# Charger_boost_LDO.net
KiCad netlist of a schematic drawn in Altium Designer
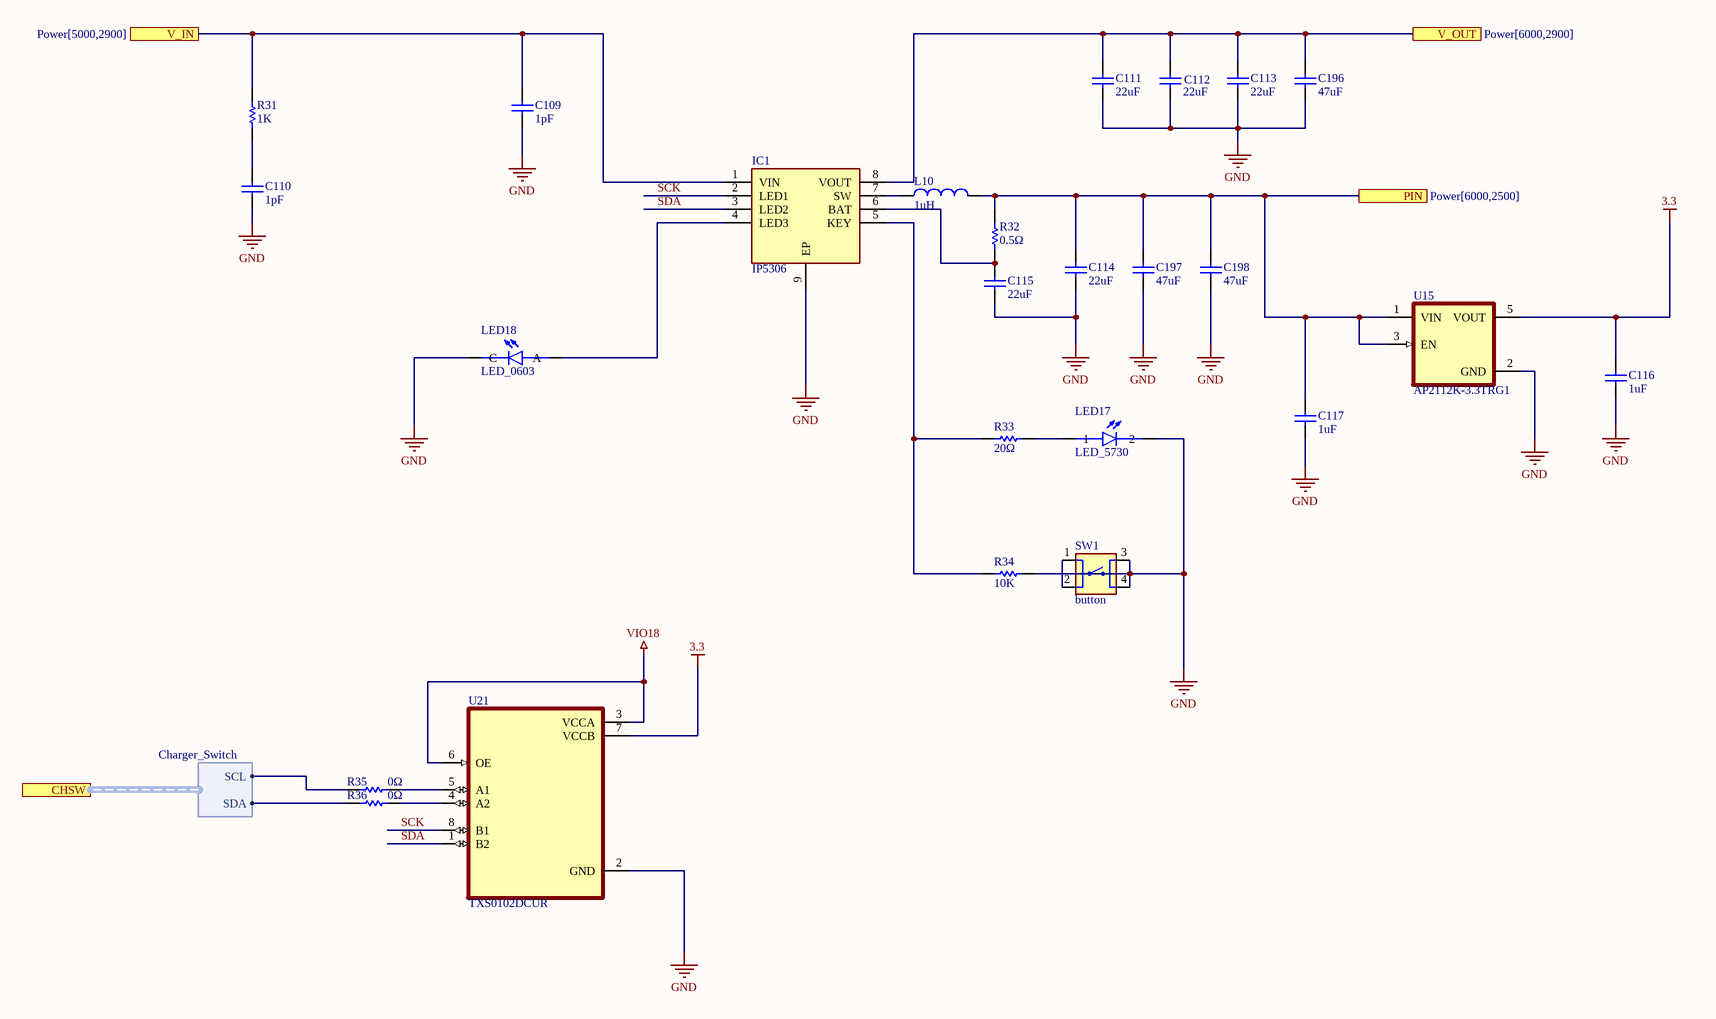
[diagram p0: Charger_boost_LDO.SchDoc]

(export (version "E")
  (design (tool "Eeschema 10.0.6"))
  (components
    (comp (ref "C109")
      (value "1pF")
      (footprint "C0402")
      (fields (field (name "Comment") "C0402"))
      (libsource (lib "kit") (part "C0402"))
    )
    (comp (ref "C110")
      (value "1pF")
      (footprint "C0402")
      (fields (field (name "Comment") "C0402"))
      (libsource (lib "kit") (part "C0402"))
    )
    (comp (ref "C111")
      (value "22uF")
      (footprint "C1210")
      (fields (field (name "Comment") "C1210"))
      (libsource (lib "kit") (part "C1210"))
    )
    (comp (ref "C112")
      (value "22uF")
      (footprint "C1210")
      (fields (field (name "Comment") "C1210"))
      (libsource (lib "kit") (part "C1210"))
    )
    (comp (ref "C113")
      (value "22uF")
      (footprint "C1210")
      (fields (field (name "Comment") "C1210"))
      (libsource (lib "kit") (part "C1210"))
    )
    (comp (ref "C114")
      (value "22uF")
      (footprint "C1210")
      (fields (field (name "Comment") "C1210"))
      (libsource (lib "kit") (part "C1210"))
    )
    (comp (ref "C115")
      (value "22uF")
      (footprint "C1210")
      (fields (field (name "Comment") "C1210"))
      (libsource (lib "kit") (part "C1210"))
    )
    (comp (ref "C116")
      (value "1uF")
      (footprint "C0805")
      (fields (field (name "Comment") "C0805"))
      (libsource (lib "kit") (part "C0805"))
    )
    (comp (ref "C117")
      (value "1uF")
      (footprint "C0805")
      (fields (field (name "Comment") "C0805"))
      (libsource (lib "kit") (part "C0805"))
    )
    (comp (ref "C196")
      (value "47uF")
      (footprint "C1812")
      (fields (field (name "Comment") "C1812"))
      (libsource (lib "kit") (part "C1812"))
    )
    (comp (ref "C197")
      (value "47uF")
      (footprint "C1812")
      (fields (field (name "Comment") "C1812"))
      (libsource (lib "kit") (part "C1812"))
    )
    (comp (ref "C198")
      (value "47uF")
      (footprint "C1812")
      (fields (field (name "Comment") "C1812"))
      (libsource (lib "kit") (part "C1812"))
    )
    (comp (ref "IC1")
      (value "IP5306")
      (footprint "SOIC127P600X165-9N")
      (description "Integrated Circuit")
      (libsource (lib "kit") (part "IP5306"))
    )
    (comp (ref "L10")
      (value "1uH")
      (footprint "L0806")
      (description "Inductor\r\nSMD:1.6x2mm")
      (fields (field (name "Comment") "L0806"))
      (libsource (lib "kit") (part "L0806"))
    )
    (comp (ref "LED17")
      (value "LED_5730")
      (footprint "SM5730UWDC05")
      (description "LED SMD")
      (fields
        (field (name "MANUFACTURER_PART_NUMBER") "SM5730UWDC05")
        (field (name "MOUSER PART NUMBER") "749-SM5730UWDC05")
      )
      (libsource (lib "kit") (part "LED_5730"))
    )
    (comp (ref "LED18")
      (value "LED_0603")
      (footprint "LED_0603")
      (description "LED SMD")
      (libsource (lib "kit") (part "LED_0603"))
    )
    (comp (ref "R31")
      (value "1K")
      (footprint "R0603")
      (fields (field (name "Comment") "R0603"))
      (libsource (lib "kit") (part "R0603"))
    )
    (comp (ref "R32")
      (value "0.5Ω")
      (footprint "R1210")
      (fields (field (name "Comment") "R1210"))
      (libsource (lib "kit") (part "R1210"))
    )
    (comp (ref "R33")
      (value "20Ω")
      (footprint "R1206")
      (fields (field (name "Comment") "R1206"))
      (libsource (lib "kit") (part "R1206"))
    )
    (comp (ref "R34")
      (value "10K")
      (footprint "R0603")
      (fields (field (name "Comment") "R0603"))
      (libsource (lib "kit") (part "R0603"))
    )
    (comp (ref "R35")
      (value "0Ω")
      (footprint "R0603")
      (fields (field (name "Comment") "R0603"))
      (libsource (lib "kit") (part "R0603"))
    )
    (comp (ref "R36")
      (value "0Ω")
      (footprint "R0603")
      (fields (field (name "Comment") "R0603"))
      (libsource (lib "kit") (part "R0603"))
    )
    (comp (ref "SW1")
      (value "button")
      (footprint "BUTTON")
      (description "6x6 mm")
      (libsource (lib "kit") (part "button"))
    )
    (comp (ref "U15")
      (value "AP2112K-3.3TRG1")
      (footprint "SOT95P285X140-5N")
      (description "Linear Voltage Regulator IC Positive Fixed 1 Output 600mA SOT-25")
      (libsource (lib "kit") (part "AP2112K-3.3TRG1"))
    )
    (comp (ref "U21")
      (value "TXS0102DCUR")
      (footprint "SOP50P310X90-8N")
      (description "chuyển mức tín hiệu I2C")
      (libsource (lib "kit") (part "TXS0102DCUR"))
    )
  )
  (nets
    (net (code "2") (name "/PIN") (class "Default")
      (node (ref "C114") (pin "2") (pinfunction "2_2") (pintype "passive"))
      (node (ref "C117") (pin "2") (pinfunction "2_2") (pintype "passive"))
      (node (ref "C197") (pin "2") (pinfunction "2_2") (pintype "passive"))
      (node (ref "C198") (pin "2") (pinfunction "2_2") (pintype "passive"))
      (node (ref "L10") (pin "2") (pinfunction "2_2") (pintype "passive"))
      (node (ref "R32") (pin "2") (pinfunction "2_2") (pintype "passive"))
      (node (ref "U15") (pin "1") (pinfunction "VIN_1") (pintype "power_in"))
      (node (ref "U15") (pin "3") (pinfunction "EN_3") (pintype "input"))
    )
    (net (code "3") (name "/SCK") (class "Default")
      (node (ref "IC1") (pin "2") (pinfunction "LED1_2") (pintype "passive"))
      (node (ref "U21") (pin "8") (pinfunction "B1_8") (pintype "bidirectional"))
    )
    (net (code "4") (name "/SCL") (class "Default")
      (node (ref "R35") (pin "1") (pinfunction "1_1") (pintype "passive"))
    )
    (net (code "5") (name "/SDA") (class "Default")
      (node (ref "IC1") (pin "3") (pinfunction "LED2_3") (pintype "passive"))
      (node (ref "U21") (pin "1") (pinfunction "B2_1") (pintype "bidirectional"))
    )
    (net (code "6") (name "/V_IN") (class "Default")
      (node (ref "C109") (pin "2") (pinfunction "2_2") (pintype "passive"))
      (node (ref "IC1") (pin "1") (pinfunction "VIN_1") (pintype "passive"))
      (node (ref "R31") (pin "2") (pinfunction "2_2") (pintype "passive"))
    )
    (net (code "7") (name "/V_OUT") (class "Default")
      (node (ref "C111") (pin "2") (pinfunction "2_2") (pintype "passive"))
      (node (ref "C112") (pin "2") (pinfunction "2_2") (pintype "passive"))
      (node (ref "C113") (pin "2") (pinfunction "2_2") (pintype "passive"))
      (node (ref "C196") (pin "2") (pinfunction "2_2") (pintype "passive"))
      (node (ref "IC1") (pin "8") (pinfunction "VOUT_8") (pintype "passive"))
    )
    (net (code "9") (name "3.3") (class "Default")
      (node (ref "C116") (pin "2") (pinfunction "2_2") (pintype "passive"))
      (node (ref "U15") (pin "5") (pinfunction "VOUT_5") (pintype "power_in"))
      (node (ref "U21") (pin "7") (pinfunction "VCCB_7") (pintype "power_in"))
    )
    (net (code "10") (name "GND") (class "Default")
      (node (ref "C109") (pin "1") (pinfunction "1_1") (pintype "passive"))
      (node (ref "C110") (pin "1") (pinfunction "1_1") (pintype "passive"))
      (node (ref "C111") (pin "1") (pinfunction "1_1") (pintype "passive"))
      (node (ref "C112") (pin "1") (pinfunction "1_1") (pintype "passive"))
      (node (ref "C113") (pin "1") (pinfunction "1_1") (pintype "passive"))
      (node (ref "C114") (pin "1") (pinfunction "1_1") (pintype "passive"))
      (node (ref "C115") (pin "1") (pinfunction "1_1") (pintype "passive"))
      (node (ref "C116") (pin "1") (pinfunction "1_1") (pintype "passive"))
      (node (ref "C117") (pin "1") (pinfunction "1_1") (pintype "passive"))
      (node (ref "C196") (pin "1") (pinfunction "1_1") (pintype "passive"))
      (node (ref "C197") (pin "1") (pinfunction "1_1") (pintype "passive"))
      (node (ref "C198") (pin "1") (pinfunction "1_1") (pintype "passive"))
      (node (ref "IC1") (pin "9") (pinfunction "EP_9") (pintype "passive"))
      (node (ref "LED17") (pin "2") (pinfunction "2_2") (pintype "passive"))
      (node (ref "LED18") (pin "C") (pinfunction "C_C") (pintype "passive"))
      (node (ref "R34") (pin "2") (pinfunction "2_2") (pintype "passive"))
      (node (ref "SW1") (pin "3") (pinfunction "3_3") (pintype "passive"))
      (node (ref "SW1") (pin "4") (pinfunction "4_4") (pintype "passive"))
      (node (ref "U15") (pin "2") (pinfunction "GND_2") (pintype "power_in"))
      (node (ref "U21") (pin "2") (pinfunction "GND_2") (pintype "power_in"))
    )
    (net (code "11") (name "Net-(C110-Pad2)") (class "Default")
      (node (ref "C110") (pin "2") (pinfunction "2_2") (pintype "passive"))
      (node (ref "R31") (pin "1") (pinfunction "1_1") (pintype "passive"))
    )
    (net (code "12") (name "Net-(IC1-BAT)") (class "Default")
      (node (ref "C115") (pin "2") (pinfunction "2_2") (pintype "passive"))
      (node (ref "IC1") (pin "6") (pinfunction "BAT_6") (pintype "passive"))
      (node (ref "R32") (pin "1") (pinfunction "1_1") (pintype "passive"))
    )
    (net (code "13") (name "Net-(IC1-KEY)") (class "Default")
      (node (ref "IC1") (pin "5") (pinfunction "KEY_5") (pintype "passive"))
      (node (ref "R33") (pin "1") (pinfunction "1_1") (pintype "passive"))
      (node (ref "R34") (pin "1") (pinfunction "1_1") (pintype "passive"))
    )
    (net (code "14") (name "Net-(IC1-LED3)") (class "Default")
      (node (ref "IC1") (pin "4") (pinfunction "LED3_4") (pintype "passive"))
      (node (ref "LED18") (pin "A") (pinfunction "A_A") (pintype "passive"))
    )
    (net (code "15") (name "Net-(IC1-SW)") (class "Default")
      (node (ref "IC1") (pin "7") (pinfunction "SW_7") (pintype "passive"))
      (node (ref "L10") (pin "1") (pinfunction "1_1") (pintype "passive"))
    )
    (net (code "16") (name "Net-(LED17-Pad1)") (class "Default")
      (node (ref "LED17") (pin "1") (pinfunction "1_1") (pintype "passive"))
      (node (ref "R33") (pin "2") (pinfunction "2_2") (pintype "passive"))
    )
    (net (code "17") (name "Net-(SW1-Pad1)") (class "Default")
      (node (ref "SW1") (pin "1") (pinfunction "1_1") (pintype "passive"))
      (node (ref "SW1") (pin "2") (pinfunction "2_2") (pintype "passive"))
    )
    (net (code "18") (name "Net-(U21-A1)") (class "Default")
      (node (ref "R35") (pin "2") (pinfunction "2_2") (pintype "passive"))
      (node (ref "U21") (pin "5") (pinfunction "A1_5") (pintype "bidirectional"))
    )
    (net (code "19") (name "Net-(U21-A2)") (class "Default")
      (node (ref "R36") (pin "2") (pinfunction "2_2") (pintype "passive"))
      (node (ref "U21") (pin "4") (pinfunction "A2_4") (pintype "bidirectional"))
    )
    (net (code "20") (name "VIO18") (class "Default")
      (node (ref "U21") (pin "3") (pinfunction "VCCA_3") (pintype "power_in"))
      (node (ref "U21") (pin "6") (pinfunction "OE_6") (pintype "input"))
    )
    (net (code "21") (name "unconnected-(R36-Pad1)") (class "Default")
      (node (ref "R36") (pin "1") (pinfunction "1_1") (pintype "passive"))
    )
  )
)
